# mother_card_17.net
KiCad netlist of a schematic drawn in EAGLE
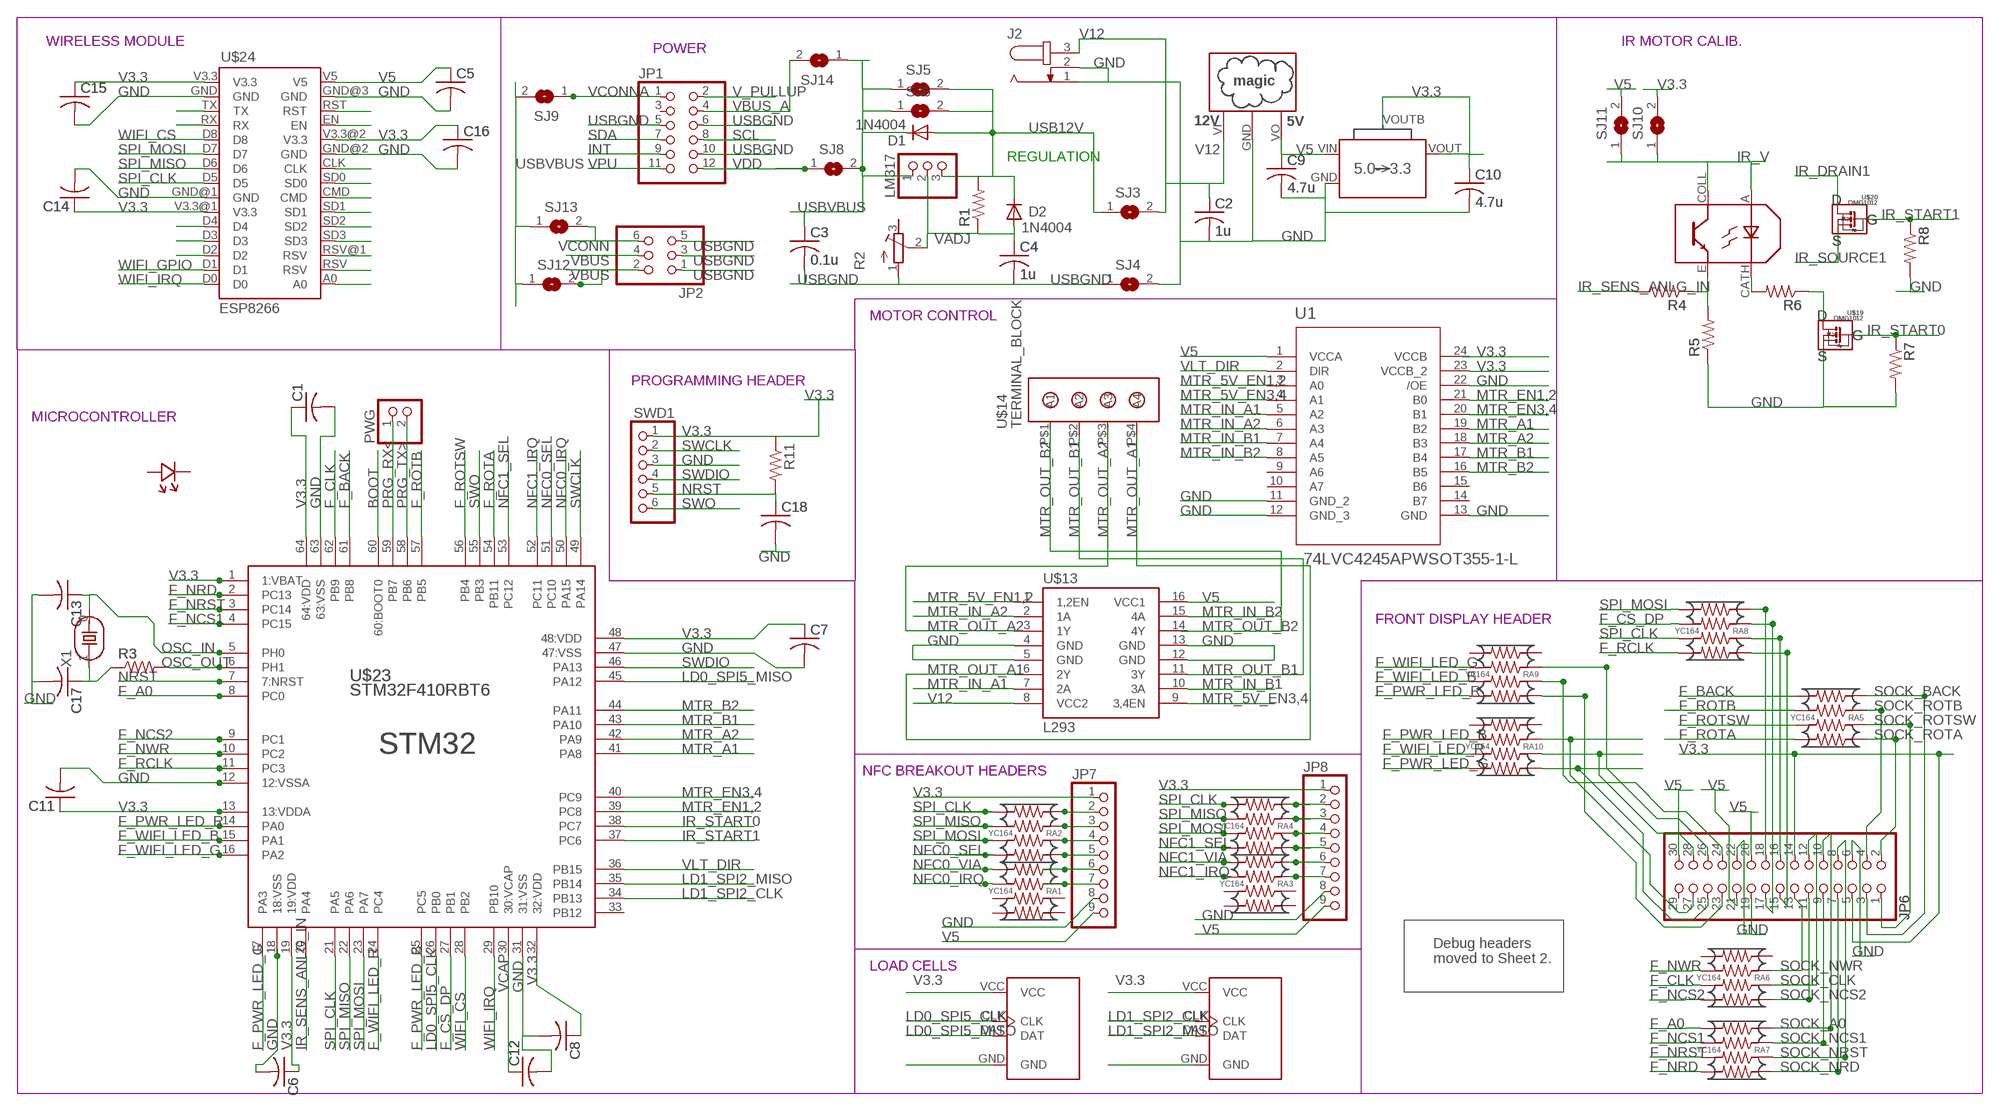
[diagram p0: schematic, sheet 1]
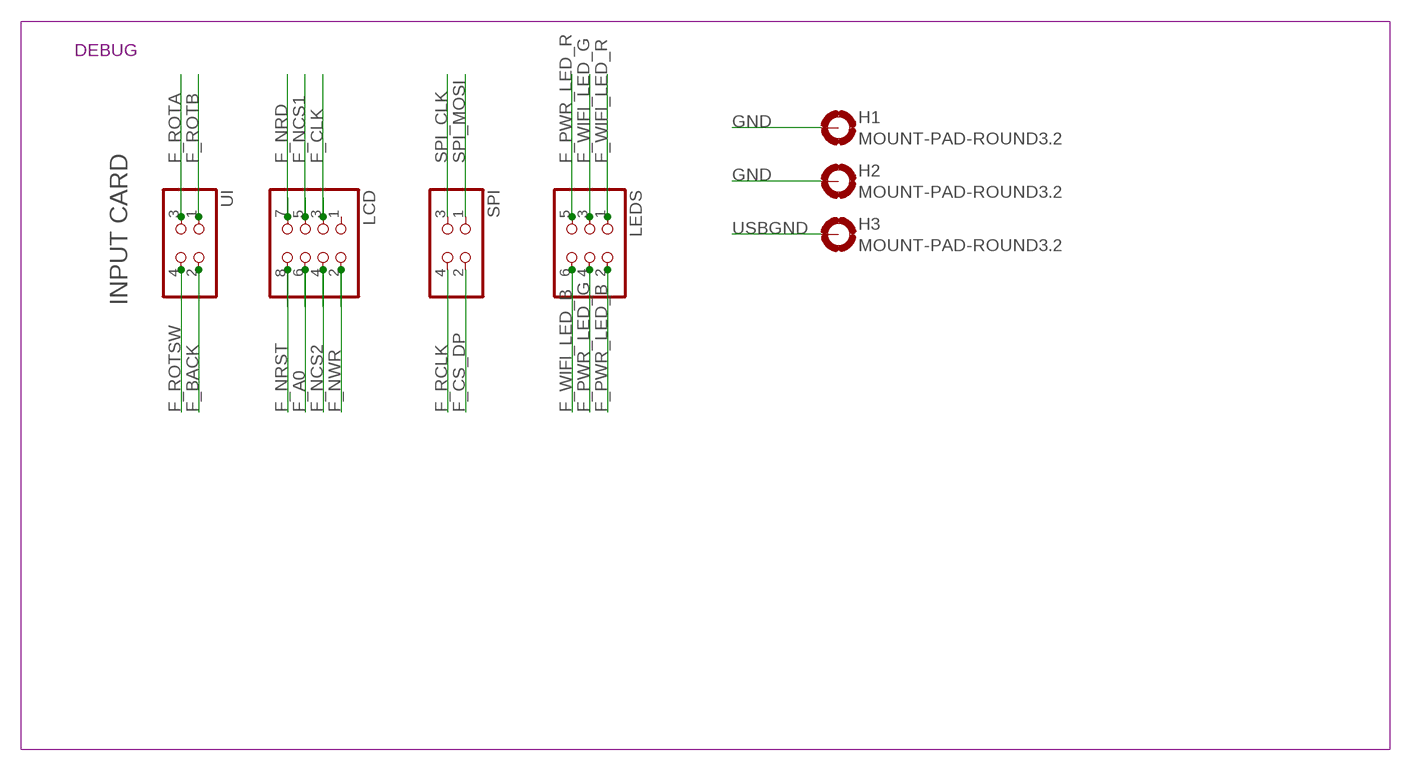
[diagram p1: schematic, sheet 2]

(export (version "E")
  (design (tool "Eeschema 10.0.6"))
  (components
    (comp (ref "H1")
      (value "MOUNT-PAD-ROUND3.2")
      (footprint "eagle-import:3,2-PAD")
      (libsource (lib "eagle-import") (part "MOUNT-PAD-ROUND3.2"))
    )
    (comp (ref "H2")
      (value "MOUNT-PAD-ROUND3.2")
      (footprint "eagle-import:3,2-PAD")
      (libsource (lib "eagle-import") (part "MOUNT-PAD-ROUND3.2"))
    )
    (comp (ref "H3")
      (value "MOUNT-PAD-ROUND3.2")
      (footprint "eagle-import:3,2-PAD")
      (libsource (lib "eagle-import") (part "MOUNT-PAD-ROUND3.2"))
    )
    (comp (ref "LCD")
      (value "PINHD-2X4")
      (footprint "eagle-import:2X04")
      (libsource (lib "eagle-import") (part "PINHD-2X4"))
    )
    (comp (ref "LEDS")
      (value "PINHD-2X3")
      (footprint "eagle-import:2X03")
      (libsource (lib "eagle-import") (part "PINHD-2X3"))
    )
    (comp (ref "SPI")
      (value "PINHD-2X2")
      (footprint "eagle-import:2X02")
      (libsource (lib "eagle-import") (part "PINHD-2X2"))
    )
    (comp (ref "UI")
      (value "PINHD-2X2")
      (footprint "eagle-import:2X02")
      (libsource (lib "eagle-import") (part "PINHD-2X2"))
    )
    (comp (ref "C1")
      (value "C-USC0805")
      (footprint "eagle-import:C0805")
      (libsource (lib "eagle-import") (part "C-USC0805"))
    )
    (comp (ref "C2")
      (value "1u")
      (footprint "eagle-import:C0805")
      (libsource (lib "eagle-import") (part "C-USC0805"))
    )
    (comp (ref "C3")
      (value "0.1u")
      (footprint "eagle-import:C0805")
      (libsource (lib "eagle-import") (part "C-USC0805"))
    )
    (comp (ref "C4")
      (value "1u")
      (footprint "eagle-import:C0805")
      (libsource (lib "eagle-import") (part "C-USC0805"))
    )
    (comp (ref "C5")
      (value "C-USC0805")
      (footprint "eagle-import:C0805")
      (libsource (lib "eagle-import") (part "C-USC0805"))
    )
    (comp (ref "C6")
      (value "C-USC0805")
      (footprint "eagle-import:C0805")
      (libsource (lib "eagle-import") (part "C-USC0805"))
    )
    (comp (ref "C7")
      (value "C-USC0805")
      (footprint "eagle-import:C0805")
      (libsource (lib "eagle-import") (part "C-USC0805"))
    )
    (comp (ref "C8")
      (value "C-USC0805")
      (footprint "eagle-import:C0805")
      (libsource (lib "eagle-import") (part "C-USC0805"))
    )
    (comp (ref "C9")
      (value "4.7u")
      (footprint "eagle-import:C0805")
      (libsource (lib "eagle-import") (part "C-USC0805"))
    )
    (comp (ref "C10")
      (value "4.7u")
      (footprint "eagle-import:C0805")
      (libsource (lib "eagle-import") (part "C-USC0805"))
    )
    (comp (ref "C11")
      (value "C-USC0805")
      (footprint "eagle-import:C0805")
      (libsource (lib "eagle-import") (part "C-USC0805"))
    )
    (comp (ref "C12")
      (value "C-USC0805")
      (footprint "eagle-import:C0805")
      (libsource (lib "eagle-import") (part "C-USC0805"))
    )
    (comp (ref "C13")
      (value "C-USC0603")
      (footprint "eagle-import:C0603")
      (libsource (lib "eagle-import") (part "C-USC0603"))
    )
    (comp (ref "C14")
      (value "C-USC0805")
      (footprint "eagle-import:C0805")
      (libsource (lib "eagle-import") (part "C-USC0805"))
    )
    (comp (ref "C15")
      (value "C-USC0805")
      (footprint "eagle-import:C0805")
      (libsource (lib "eagle-import") (part "C-USC0805"))
    )
    (comp (ref "C16")
      (value "C-USC0805")
      (footprint "eagle-import:C0805")
      (libsource (lib "eagle-import") (part "C-USC0805"))
    )
    (comp (ref "C17")
      (value "C-USC0603")
      (footprint "eagle-import:C0603")
      (libsource (lib "eagle-import") (part "C-USC0603"))
    )
    (comp (ref "C18")
      (value "C-USC0805")
      (footprint "eagle-import:C0805")
      (libsource (lib "eagle-import") (part "C-USC0805"))
    )
    (comp (ref "D1")
      (value "1N4004")
      (footprint "eagle-import:DO41-10")
      (libsource (lib "eagle-import") (part "1N4004"))
    )
    (comp (ref "D2")
      (value "1N4004")
      (footprint "eagle-import:DO41-10")
      (libsource (lib "eagle-import") (part "1N4004"))
    )
    (comp (ref "J2")
      (value "JACK-PLUG0")
      (footprint "eagle-import:SPC4077")
      (libsource (lib "eagle-import") (part "JACK-PLUG0"))
    )
    (comp (ref "JP1")
      (value "PINHD-2X6")
      (footprint "eagle-import:2X06")
      (libsource (lib "eagle-import") (part "PINHD-2X6"))
    )
    (comp (ref "JP2")
      (value "PINHD-2X3")
      (footprint "eagle-import:2X03")
      (libsource (lib "eagle-import") (part "PINHD-2X3"))
    )
    (comp (ref "JP6")
      (value "PINHD-2X15/SOCK")
      (footprint "eagle-import:2X15_SOCK")
      (libsource (lib "eagle-import") (part "PINHD-2X15/SOCK"))
    )
    (comp (ref "JP7")
      (value "PINHD-1X9/90")
      (footprint "eagle-import:1X09_90")
      (libsource (lib "eagle-import") (part "PINHD-1X9/90"))
    )
    (comp (ref "JP8")
      (value "PINHD-1X9/90")
      (footprint "eagle-import:1X09_90")
      (libsource (lib "eagle-import") (part "PINHD-1X9/90"))
    )
    (comp (ref "LM317")
      (value "PINHD-1X3")
      (footprint "eagle-import:1X03")
      (libsource (lib "eagle-import") (part "PINHD-1X3"))
    )
    (comp (ref "PWG")
      (value "PINHD-1X2")
      (footprint "eagle-import:1X02")
      (libsource (lib "eagle-import") (part "PINHD-1X2"))
    )
    (comp (ref "R1")
      (value "R-US_R0805")
      (footprint "eagle-import:R0805")
      (libsource (lib "eagle-import") (part "seniorDesign_R-US_R0805"))
    )
    (comp (ref "R2")
      (value "R-TRIMM64W")
      (footprint "eagle-import:RTRIM64W")
      (libsource (lib "eagle-import") (part "R-TRIMM64W"))
    )
    (comp (ref "R3")
      (value "R-US_R0805")
      (footprint "eagle-import:R0805")
      (libsource (lib "eagle-import") (part "seniorDesign_R-US_R0805"))
    )
    (comp (ref "R4")
      (value "R-US_R0805")
      (footprint "eagle-import:R0805")
      (libsource (lib "eagle-import") (part "seniorDesign_R-US_R0805"))
    )
    (comp (ref "R5")
      (value "R-US_R0805")
      (footprint "eagle-import:R0805")
      (libsource (lib "eagle-import") (part "seniorDesign_R-US_R0805"))
    )
    (comp (ref "R6")
      (value "R-US_R0805")
      (footprint "eagle-import:R0805")
      (libsource (lib "eagle-import") (part "seniorDesign_R-US_R0805"))
    )
    (comp (ref "R7")
      (value "R-US_R0805")
      (footprint "eagle-import:R0805")
      (libsource (lib "eagle-import") (part "seniorDesign_R-US_R0805"))
    )
    (comp (ref "R8")
      (value "R-US_R0805")
      (footprint "eagle-import:R0805")
      (libsource (lib "eagle-import") (part "seniorDesign_R-US_R0805"))
    )
    (comp (ref "R11")
      (value "R-US_R0805")
      (footprint "eagle-import:R0805")
      (libsource (lib "eagle-import") (part "R-US_R0805"))
    )
    (comp (ref "RA1")
      (value "YC164")
      (footprint "eagle-import:YC164")
      (libsource (lib "eagle-import") (part "YC164"))
    )
    (comp (ref "RA2")
      (value "YC164")
      (footprint "eagle-import:YC164")
      (libsource (lib "eagle-import") (part "YC164"))
    )
    (comp (ref "RA3")
      (value "YC164")
      (footprint "eagle-import:YC164")
      (libsource (lib "eagle-import") (part "YC164"))
    )
    (comp (ref "RA4")
      (value "YC164")
      (footprint "eagle-import:YC164")
      (libsource (lib "eagle-import") (part "YC164"))
    )
    (comp (ref "RA5")
      (value "YC164")
      (footprint "eagle-import:YC164")
      (libsource (lib "eagle-import") (part "YC164"))
    )
    (comp (ref "RA6")
      (value "YC164")
      (footprint "eagle-import:YC164")
      (libsource (lib "eagle-import") (part "YC164"))
    )
    (comp (ref "RA7")
      (value "YC164")
      (footprint "eagle-import:YC164")
      (libsource (lib "eagle-import") (part "YC164"))
    )
    (comp (ref "RA8")
      (value "YC164")
      (footprint "eagle-import:YC164")
      (libsource (lib "eagle-import") (part "YC164"))
    )
    (comp (ref "RA9")
      (value "YC164")
      (footprint "eagle-import:YC164")
      (libsource (lib "eagle-import") (part "YC164"))
    )
    (comp (ref "RA10")
      (value "YC164")
      (footprint "eagle-import:YC164")
      (libsource (lib "eagle-import") (part "YC164"))
    )
    (comp (ref "SJ3") (value "SJ") (footprint "eagle-import:SJ") (libsource (lib "eagle-import") (part "SJ")))
    (comp (ref "SJ4") (value "SJ") (footprint "eagle-import:SJ") (libsource (lib "eagle-import") (part "SJ")))
    (comp (ref "SJ5") (value "SJ") (footprint "eagle-import:SJ") (libsource (lib "eagle-import") (part "SJ")))
    (comp (ref "SJ6") (value "SJ") (footprint "eagle-import:SJ") (libsource (lib "eagle-import") (part "SJ")))
    (comp (ref "SJ8") (value "SJ") (footprint "eagle-import:SJ") (libsource (lib "eagle-import") (part "SJ")))
    (comp (ref "SJ9") (value "SJ") (footprint "eagle-import:SJ") (libsource (lib "eagle-import") (part "SJ")))
    (comp (ref "SJ10")
      (value "SJ")
      (footprint "eagle-import:SJ")
      (libsource (lib "eagle-import") (part "SJ"))
    )
    (comp (ref "SJ11")
      (value "SJ")
      (footprint "eagle-import:SJ")
      (libsource (lib "eagle-import") (part "SJ"))
    )
    (comp (ref "SJ12")
      (value "SJ")
      (footprint "eagle-import:SJ")
      (libsource (lib "eagle-import") (part "SJ"))
    )
    (comp (ref "SJ13")
      (value "SJ")
      (footprint "eagle-import:SJ")
      (libsource (lib "eagle-import") (part "SJ"))
    )
    (comp (ref "SJ14")
      (value "SJ")
      (footprint "eagle-import:SJ")
      (libsource (lib "eagle-import") (part "SJ"))
    )
    (comp (ref "SWD1")
      (value "PINHD-1X6")
      (footprint "eagle-import:1X06")
      (libsource (lib "eagle-import") (part "PINHD-1X6"))
    )
    (comp (ref "U$12")
      (value "LED0603")
      (footprint "eagle-import:LED")
      (libsource (lib "eagle-import") (part "LED0603"))
    )
    (comp (ref "U$13")
      (value "L293")
      (footprint "eagle-import:DIL16")
      (libsource (lib "eagle-import") (part "L293"))
    )
    (comp (ref "U$14")
      (value "TERMINAL_BLOCK")
      (footprint "eagle-import:1X4_BLOCK")
      (libsource (lib "eagle-import") (part "TERMINAL_BLOCK"))
    )
    (comp (ref "U$15")
      (value "AP2114H")
      (footprint "eagle-import:AP2114H")
      (libsource (lib "eagle-import") (part "AP2114H"))
    )
    (comp (ref "U$16")
      (value "OKI-78SR-W36")
      (footprint "eagle-import:SIP3")
      (libsource (lib "eagle-import") (part "OKI-78SR-W36"))
    )
    (comp (ref "U$18")
      (value "TCRT5000")
      (footprint "eagle-import:TCRT5000")
      (libsource (lib "eagle-import") (part "TCRT5000"))
    )
    (comp (ref "U$19")
      (value "DMG1012")
      (footprint "eagle-import:SOT323")
      (libsource (lib "eagle-import") (part "DMG1012"))
    )
    (comp (ref "U$20")
      (value "DMG1012")
      (footprint "eagle-import:SOT323")
      (libsource (lib "eagle-import") (part "DMG1012"))
    )
    (comp (ref "U$21")
      (value "HX711")
      (footprint "eagle-import:HX711")
      (libsource (lib "eagle-import") (part "HX711"))
    )
    (comp (ref "U$22")
      (value "HX711")
      (footprint "eagle-import:HX711")
      (libsource (lib "eagle-import") (part "HX711"))
    )
    (comp (ref "U$23")
      (value "STM32F410RBT6")
      (footprint "eagle-import:QFP50P1200X1200X160-64N")
      (libsource (lib "eagle-import") (part "STM32F410RBT6"))
    )
    (comp (ref "U$24")
      (value "ESP8266")
      (footprint "eagle-import:ESP8266")
      (libsource (lib "eagle-import") (part "ESP8266"))
    )
    (comp (ref "U1")
      (value "74LVC4245APWSOT355-1-L")
      (footprint "eagle-import:SOT355-1-L")
      (fields (field (name "MANUFACTURER_PART_NUMBER") "74LVC4245APW"))
      (libsource (lib "eagle-import") (part "74LVC4245APWSOT355-1-L"))
    )
    (comp (ref "X1")
      (value "HC-49S_9B")
      (footprint "eagle-import:HC-49S_9B")
      (libsource (lib "eagle-import") (part "HC-49S_9B"))
    )
  )
  (nets
    (net (code "1") (name "BOOT") (class "Default")
      (node (ref "U$23") (pin "60") (pinfunction "60:BOOT0_60") (pintype "bidirectional"))
    )
    (net (code "2") (name "F_A0") (class "Default")
      (node (ref "LCD") (pin "6") (pinfunction "6_6") (pintype "passive"))
      (node (ref "RA7") (pin "P$4") (pinfunction "4_P$4") (pintype "passive"))
      (node (ref "U$23") (pin "8") (pinfunction "PC0_8") (pintype "bidirectional"))
    )
    (net (code "3") (name "F_BACK") (class "Default")
      (node (ref "RA5") (pin "P$4") (pinfunction "4_P$4") (pintype "passive"))
      (node (ref "U$23") (pin "61") (pinfunction "PB8_61") (pintype "bidirectional"))
      (node (ref "UI") (pin "2") (pinfunction "2_2") (pintype "passive"))
    )
    (net (code "4") (name "F_CLK") (class "Default")
      (node (ref "LCD") (pin "3") (pinfunction "3_3") (pintype "passive"))
      (node (ref "RA6") (pin "P$2") (pinfunction "2_P$2") (pintype "passive"))
      (node (ref "U$23") (pin "62") (pinfunction "PB9_62") (pintype "bidirectional"))
    )
    (net (code "5") (name "F_CS_DP") (class "Default")
      (node (ref "RA8") (pin "P$3") (pinfunction "3_P$3") (pintype "passive"))
      (node (ref "SPI") (pin "2") (pinfunction "2_2") (pintype "passive"))
      (node (ref "U$23") (pin "27") (pinfunction "PB1_27") (pintype "bidirectional"))
    )
    (net (code "6") (name "F_NCS1") (class "Default")
      (node (ref "LCD") (pin "5") (pinfunction "5_5") (pintype "passive"))
      (node (ref "RA7") (pin "P$3") (pinfunction "3_P$3") (pintype "passive"))
      (node (ref "U$23") (pin "4") (pinfunction "PC15_4") (pintype "bidirectional"))
    )
    (net (code "7") (name "F_NCS2") (class "Default")
      (node (ref "LCD") (pin "4") (pinfunction "4_4") (pintype "passive"))
      (node (ref "RA6") (pin "P$1") (pinfunction "1_P$1") (pintype "passive"))
      (node (ref "U$23") (pin "9") (pinfunction "PC1_9") (pintype "bidirectional"))
    )
    (net (code "8") (name "F_NRD") (class "Default")
      (node (ref "LCD") (pin "7") (pinfunction "7_7") (pintype "passive"))
      (node (ref "RA7") (pin "P$1") (pinfunction "1_P$1") (pintype "passive"))
      (node (ref "U$23") (pin "2") (pinfunction "PC13_2") (pintype "bidirectional"))
    )
    (net (code "9") (name "F_NRST") (class "Default")
      (node (ref "LCD") (pin "8") (pinfunction "8_8") (pintype "passive"))
      (node (ref "RA7") (pin "P$2") (pinfunction "2_P$2") (pintype "passive"))
      (node (ref "U$23") (pin "3") (pinfunction "PC14_3") (pintype "bidirectional"))
    )
    (net (code "10") (name "F_NWR") (class "Default")
      (node (ref "LCD") (pin "2") (pinfunction "2_2") (pintype "passive"))
      (node (ref "RA6") (pin "P$3") (pinfunction "3_P$3") (pintype "passive"))
      (node (ref "U$23") (pin "10") (pinfunction "PC2_10") (pintype "bidirectional"))
    )
    (net (code "11") (name "F_PWR_LED_B") (class "Default")
      (node (ref "LEDS") (pin "2") (pinfunction "2_2") (pintype "passive"))
      (node (ref "RA10") (pin "P$3") (pinfunction "3_P$3") (pintype "passive"))
      (node (ref "U$23") (pin "25") (pinfunction "PC5_25") (pintype "bidirectional"))
    )
    (net (code "12") (name "F_PWR_LED_G") (class "Default")
      (node (ref "LEDS") (pin "4") (pinfunction "4_4") (pintype "passive"))
      (node (ref "RA10") (pin "P$1") (pinfunction "1_P$1") (pintype "passive"))
      (node (ref "U$23") (pin "17") (pinfunction "PA3_17") (pintype "bidirectional"))
    )
    (net (code "13") (name "F_PWR_LED_R") (class "Default")
      (node (ref "LEDS") (pin "5") (pinfunction "5_5") (pintype "passive"))
      (node (ref "RA9") (pin "P$1") (pinfunction "1_P$1") (pintype "passive"))
      (node (ref "U$23") (pin "14") (pinfunction "PA0_14") (pintype "bidirectional"))
    )
    (net (code "14") (name "F_RCLK") (class "Default")
      (node (ref "RA8") (pin "P$1") (pinfunction "1_P$1") (pintype "passive"))
      (node (ref "SPI") (pin "4") (pinfunction "4_4") (pintype "passive"))
      (node (ref "U$23") (pin "11") (pinfunction "PC3_11") (pintype "bidirectional"))
    )
    (net (code "15") (name "F_ROTA") (class "Default")
      (node (ref "RA5") (pin "P$1") (pinfunction "1_P$1") (pintype "passive"))
      (node (ref "U$23") (pin "54") (pinfunction "PB11_54") (pintype "bidirectional"))
      (node (ref "UI") (pin "3") (pinfunction "3_3") (pintype "passive"))
    )
    (net (code "16") (name "F_ROTB") (class "Default")
      (node (ref "RA5") (pin "P$3") (pinfunction "3_P$3") (pintype "passive"))
      (node (ref "U$23") (pin "57") (pinfunction "PB5_57") (pintype "bidirectional"))
      (node (ref "UI") (pin "1") (pinfunction "1_1") (pintype "passive"))
    )
    (net (code "17") (name "F_ROTSW") (class "Default")
      (node (ref "RA5") (pin "P$2") (pinfunction "2_P$2") (pintype "passive"))
      (node (ref "U$23") (pin "56") (pinfunction "PB4_56") (pintype "bidirectional"))
      (node (ref "UI") (pin "4") (pinfunction "4_4") (pintype "passive"))
    )
    (net (code "18") (name "F_WIFI_LED_B") (class "Default")
      (node (ref "LEDS") (pin "6") (pinfunction "6_6") (pintype "passive"))
      (node (ref "RA9") (pin "P$2") (pinfunction "2_P$2") (pintype "passive"))
      (node (ref "U$23") (pin "15") (pinfunction "PA1_15") (pintype "bidirectional"))
    )
    (net (code "19") (name "F_WIFI_LED_G") (class "Default")
      (node (ref "LEDS") (pin "3") (pinfunction "3_3") (pintype "passive"))
      (node (ref "RA9") (pin "P$3") (pinfunction "3_P$3") (pintype "passive"))
      (node (ref "U$23") (pin "16") (pinfunction "PA2_16") (pintype "bidirectional"))
    )
    (net (code "20") (name "F_WIFI_LED_R") (class "Default")
      (node (ref "LEDS") (pin "1") (pinfunction "1_1") (pintype "passive"))
      (node (ref "RA10") (pin "P$2") (pinfunction "2_P$2") (pintype "passive"))
      (node (ref "U$23") (pin "24") (pinfunction "PC4_24") (pintype "bidirectional"))
    )
    (net (code "21") (name "GND") (class "Default")
      (node (ref "C1") (pin "2") (pinfunction "2_2") (pintype "passive"))
      (node (ref "C10") (pin "2") (pinfunction "2_2") (pintype "passive"))
      (node (ref "C11") (pin "2") (pinfunction "2_2") (pintype "passive"))
      (node (ref "C12") (pin "2") (pinfunction "2_2") (pintype "passive"))
      (node (ref "C13") (pin "2") (pinfunction "2_2") (pintype "passive"))
      (node (ref "C14") (pin "2") (pinfunction "2_2") (pintype "passive"))
      (node (ref "C15") (pin "2") (pinfunction "2_2") (pintype "passive"))
      (node (ref "C16") (pin "2") (pinfunction "2_2") (pintype "passive"))
      (node (ref "C17") (pin "2") (pinfunction "2_2") (pintype "passive"))
      (node (ref "C18") (pin "2") (pinfunction "2_2") (pintype "passive"))
      (node (ref "C2") (pin "2") (pinfunction "2_2") (pintype "passive"))
      (node (ref "C5") (pin "2") (pinfunction "2_2") (pintype "passive"))
      (node (ref "C6") (pin "2") (pinfunction "2_2") (pintype "passive"))
      (node (ref "C7") (pin "2") (pinfunction "2_2") (pintype "passive"))
      (node (ref "C8") (pin "2") (pinfunction "2_2") (pintype "passive"))
      (node (ref "C9") (pin "2") (pinfunction "2_2") (pintype "passive"))
      (node (ref "H1") (pin "B3,2") (pinfunction "MOUNT_B3,2") (pintype "passive"))
      (node (ref "H2") (pin "B3,2") (pinfunction "MOUNT_B3,2") (pintype "passive"))
      (node (ref "J2") (pin "1") (pinfunction "1_1") (pintype "passive"))
      (node (ref "J2") (pin "2") (pinfunction "2_2") (pintype "passive"))
      (node (ref "JP6") (pin "19") (pinfunction "19_19") (pintype "passive"))
      (node (ref "JP6") (pin "22") (pinfunction "22_22") (pintype "passive"))
      (node (ref "JP6") (pin "6") (pinfunction "6_6") (pintype "passive"))
      (node (ref "JP7") (pin "8") (pinfunction "8_8") (pintype "passive"))
      (node (ref "JP8") (pin "8") (pinfunction "8_8") (pintype "passive"))
      (node (ref "R5") (pin "1") (pinfunction "1_1") (pintype "passive"))
      (node (ref "R7") (pin "2") (pinfunction "2_2") (pintype "passive"))
      (node (ref "R8") (pin "2") (pinfunction "2_2") (pintype "passive"))
      (node (ref "SJ4") (pin "2") (pinfunction "2_2") (pintype "passive"))
      (node (ref "SWD1") (pin "3") (pinfunction "3_3") (pintype "passive"))
      (node (ref "U$13") (pin "12") (pinfunction "GND_12") (pintype "bidirectional"))
      (node (ref "U$13") (pin "13") (pinfunction "GND_13") (pintype "bidirectional"))
      (node (ref "U$13") (pin "4") (pinfunction "GND_4") (pintype "bidirectional"))
      (node (ref "U$13") (pin "5") (pinfunction "GND_5") (pintype "bidirectional"))
      (node (ref "U$15") (pin "GND") (pinfunction "GND_GND") (pintype "power_in"))
      (node (ref "U$16") (pin "GND") (pinfunction "P$2_GND") (pintype "power_in"))
      (node (ref "U$19") (pin "S") (pinfunction "S_S") (pintype "bidirectional"))
      (node (ref "U$21") (pin "GND") (pinfunction "GND_GND") (pintype "power_in"))
      (node (ref "U$22") (pin "GND") (pinfunction "GND_GND") (pintype "power_in"))
      (node (ref "U$23") (pin "12") (pinfunction "12:VSSA_12") (pintype "bidirectional"))
      (node (ref "U$23") (pin "18") (pinfunction "18:VSS_18") (pintype "bidirectional"))
      (node (ref "U$23") (pin "31") (pinfunction "31:VSS_31") (pintype "bidirectional"))
      (node (ref "U$23") (pin "47") (pinfunction "47:VSS_47") (pintype "bidirectional"))
      (node (ref "U$23") (pin "63") (pinfunction "63:VSS_63") (pintype "bidirectional"))
      (node (ref "U$24") (pin "GND") (pinfunction "GND_GND") (pintype "bidirectional"))
      (node (ref "U$24") (pin "GND@1") (pinfunction "GND_GND@1") (pintype "bidirectional"))
      (node (ref "U$24") (pin "GND@2") (pinfunction "GND_GND@2") (pintype "bidirectional"))
      (node (ref "U$24") (pin "GND@3") (pinfunction "GND_GND@3") (pintype "bidirectional"))
      (node (ref "U1") (pin "11") (pinfunction "GND_2_11") (pintype "power_in"))
      (node (ref "U1") (pin "12") (pinfunction "GND_3_12") (pintype "power_in"))
      (node (ref "U1") (pin "13") (pinfunction "GND_13") (pintype "power_in"))
      (node (ref "U1") (pin "22") (pinfunction "/OE_22") (pintype "input"))
    )
    (net (code "22") (name "INT") (class "Default")
      (node (ref "JP1") (pin "9") (pinfunction "9_9") (pintype "passive"))
    )
    (net (code "23") (name "IR_DRAIN1") (class "Default")
      (node (ref "U$20") (pin "D") (pinfunction "D_D") (pintype "bidirectional"))
    )
    (net (code "24") (name "IR_SENS_ANLG_IN") (class "Default")
      (node (ref "R4") (pin "2") (pinfunction "2_2") (pintype "passive"))
      (node (ref "U$23") (pin "20") (pinfunction "PA4_20") (pintype "bidirectional"))
    )
    (net (code "25") (name "IR_SOURCE1") (class "Default")
      (node (ref "U$20") (pin "S") (pinfunction "S_S") (pintype "bidirectional"))
    )
    (net (code "26") (name "IR_START0") (class "Default")
      (node (ref "R7") (pin "1") (pinfunction "1_1") (pintype "passive"))
      (node (ref "U$19") (pin "G") (pinfunction "G_G") (pintype "bidirectional"))
      (node (ref "U$23") (pin "38") (pinfunction "PC7_38") (pintype "bidirectional"))
    )
    (net (code "27") (name "IR_START1") (class "Default")
      (node (ref "R8") (pin "1") (pinfunction "1_1") (pintype "passive"))
      (node (ref "U$20") (pin "G") (pinfunction "G_G") (pintype "bidirectional"))
      (node (ref "U$23") (pin "37") (pinfunction "PC6_37") (pintype "bidirectional"))
    )
    (net (code "28") (name "IR_V") (class "Default")
      (node (ref "SJ10") (pin "1") (pinfunction "1_1") (pintype "passive"))
      (node (ref "SJ11") (pin "1") (pinfunction "1_1") (pintype "passive"))
      (node (ref "U$18") (pin "A") (pinfunction "A_A") (pintype "bidirectional"))
      (node (ref "U$18") (pin "COLL") (pinfunction "COLL_COLL") (pintype "bidirectional"))
    )
    (net (code "29") (name "LD0_SPI5_CLK") (class "Default")
      (node (ref "U$21") (pin "CLK") (pinfunction "CLK_CLK") (pintype "bidirectional"))
      (node (ref "U$23") (pin "26") (pinfunction "PB0_26") (pintype "bidirectional"))
    )
    (net (code "30") (name "LD0_SPI5_MISO") (class "Default")
      (node (ref "U$21") (pin "DAT") (pinfunction "DAT_DAT") (pintype "bidirectional"))
      (node (ref "U$23") (pin "45") (pinfunction "PA12_45") (pintype "bidirectional"))
    )
    (net (code "31") (name "LD1_SPI2_CLK") (class "Default")
      (node (ref "U$22") (pin "CLK") (pinfunction "CLK_CLK") (pintype "bidirectional"))
      (node (ref "U$23") (pin "34") (pinfunction "PB13_34") (pintype "bidirectional"))
    )
    (net (code "32") (name "LD1_SPI2_MISO") (class "Default")
      (node (ref "U$22") (pin "DAT") (pinfunction "DAT_DAT") (pintype "bidirectional"))
      (node (ref "U$23") (pin "35") (pinfunction "PB14_35") (pintype "bidirectional"))
    )
    (net (code "33") (name "MTR_5V_EN1,2") (class "Default")
      (node (ref "U$13") (pin "1") (pinfunction "1,2EN_1") (pintype "bidirectional"))
      (node (ref "U1") (pin "3") (pinfunction "A0_3") (pintype "bidirectional"))
    )
    (net (code "34") (name "MTR_5V_EN3,4") (class "Default")
      (node (ref "U$13") (pin "9") (pinfunction "3,4EN_9") (pintype "bidirectional"))
      (node (ref "U1") (pin "4") (pinfunction "A1_4") (pintype "bidirectional"))
    )
    (net (code "35") (name "MTR_A1") (class "Default")
      (node (ref "U$23") (pin "41") (pinfunction "PA8_41") (pintype "bidirectional"))
      (node (ref "U1") (pin "19") (pinfunction "B2_19") (pintype "bidirectional"))
    )
    (net (code "36") (name "MTR_A2") (class "Default")
      (node (ref "U$23") (pin "42") (pinfunction "PA9_42") (pintype "bidirectional"))
      (node (ref "U1") (pin "18") (pinfunction "B3_18") (pintype "bidirectional"))
    )
    (net (code "37") (name "MTR_B1") (class "Default")
      (node (ref "U$23") (pin "43") (pinfunction "PA10_43") (pintype "bidirectional"))
      (node (ref "U1") (pin "17") (pinfunction "B4_17") (pintype "bidirectional"))
    )
    (net (code "38") (name "MTR_B2") (class "Default")
      (node (ref "U$23") (pin "44") (pinfunction "PA11_44") (pintype "bidirectional"))
      (node (ref "U1") (pin "16") (pinfunction "B5_16") (pintype "bidirectional"))
    )
    (net (code "39") (name "MTR_EN1,2") (class "Default")
      (node (ref "U$23") (pin "39") (pinfunction "PC8_39") (pintype "bidirectional"))
      (node (ref "U1") (pin "21") (pinfunction "B0_21") (pintype "bidirectional"))
    )
    (net (code "40") (name "MTR_EN3,4") (class "Default")
      (node (ref "U$23") (pin "40") (pinfunction "PC9_40") (pintype "bidirectional"))
      (node (ref "U1") (pin "20") (pinfunction "B1_20") (pintype "bidirectional"))
    )
    (net (code "41") (name "MTR_IN_A1") (class "Default")
      (node (ref "U$13") (pin "7") (pinfunction "2A_7") (pintype "bidirectional"))
      (node (ref "U1") (pin "5") (pinfunction "A2_5") (pintype "bidirectional"))
    )
    (net (code "42") (name "MTR_IN_A2") (class "Default")
      (node (ref "U$13") (pin "2") (pinfunction "1A_2") (pintype "bidirectional"))
      (node (ref "U1") (pin "6") (pinfunction "A3_6") (pintype "bidirectional"))
    )
    (net (code "43") (name "MTR_IN_B1") (class "Default")
      (node (ref "U$13") (pin "10") (pinfunction "3A_10") (pintype "bidirectional"))
      (node (ref "U1") (pin "7") (pinfunction "A4_7") (pintype "bidirectional"))
    )
    (net (code "44") (name "MTR_IN_B2") (class "Default")
      (node (ref "U$13") (pin "15") (pinfunction "4A_15") (pintype "bidirectional"))
      (node (ref "U1") (pin "8") (pinfunction "A5_8") (pintype "bidirectional"))
    )
    (net (code "45") (name "MTR_OUT_A1") (class "Default")
      (node (ref "U$13") (pin "6") (pinfunction "2Y_6") (pintype "bidirectional"))
      (node (ref "U$14") (pin "P$4") (pinfunction "A4_P$4") (pintype "bidirectional"))
    )
    (net (code "46") (name "MTR_OUT_A2") (class "Default")
      (node (ref "U$13") (pin "3") (pinfunction "1Y_3") (pintype "bidirectional"))
      (node (ref "U$14") (pin "P$3") (pinfunction "A3_P$3") (pintype "bidirectional"))
    )
    (net (code "47") (name "MTR_OUT_B1") (class "Default")
      (node (ref "U$13") (pin "11") (pinfunction "3Y_11") (pintype "bidirectional"))
      (node (ref "U$14") (pin "P$2") (pinfunction "A2_P$2") (pintype "bidirectional"))
    )
    (net (code "48") (name "MTR_OUT_B2") (class "Default")
      (node (ref "U$13") (pin "14") (pinfunction "4Y_14") (pintype "bidirectional"))
      (node (ref "U$14") (pin "P$1") (pinfunction "A1_P$1") (pintype "bidirectional"))
    )
    (net (code "49") (name "NFC0_IRQ") (class "Default")
      (node (ref "RA1") (pin "P$3") (pinfunction "3_P$3") (pintype "passive"))
      (node (ref "U$23") (pin "50") (pinfunction "PA15_50") (pintype "bidirectional"))
    )
    (net (code "50") (name "NFC0_SEL") (class "Default")
      (node (ref "RA2") (pin "P$1") (pinfunction "1_P$1") (pintype "passive"))
      (node (ref "U$23") (pin "51") (pinfunction "PC10_51") (pintype "bidirectional"))
    )
    (net (code "51") (name "NFC0_VIA") (class "Default")
      (node (ref "RA1") (pin "P$4") (pinfunction "4_P$4") (pintype "passive"))
    )
    (net (code "52") (name "NFC1_IRQ") (class "Default")
      (node (ref "RA3") (pin "P$3") (pinfunction "3_P$3") (pintype "passive"))
      (node (ref "U$23") (pin "52") (pinfunction "PC11_52") (pintype "bidirectional"))
    )
    (net (code "53") (name "NFC1_SEL") (class "Default")
      (node (ref "RA4") (pin "P$1") (pinfunction "1_P$1") (pintype "passive"))
      (node (ref "U$23") (pin "53") (pinfunction "PC12_53") (pintype "bidirectional"))
    )
    (net (code "54") (name "NFC1_VIA") (class "Default")
      (node (ref "RA3") (pin "P$4") (pinfunction "4_P$4") (pintype "passive"))
    )
    (net (code "55") (name "NRST") (class "Default")
      (node (ref "C18") (pin "1") (pinfunction "1_1") (pintype "passive"))
      (node (ref "R11") (pin "2") (pinfunction "2_2") (pintype "passive"))
      (node (ref "SWD1") (pin "5") (pinfunction "5_5") (pintype "passive"))
      (node (ref "U$23") (pin "7") (pinfunction "7:NRST_7") (pintype "bidirectional"))
    )
    (net (code "56") (name "Net-(R4-Pad1)") (class "Default")
      (node (ref "R4") (pin "1") (pinfunction "1_1") (pintype "passive"))
      (node (ref "R5") (pin "2") (pinfunction "2_2") (pintype "passive"))
      (node (ref "U$18") (pin "E") (pinfunction "E_E") (pintype "bidirectional"))
    )
    (net (code "57") (name "Net-(R6-Pad1)") (class "Default")
      (node (ref "R6") (pin "1") (pinfunction "1_1") (pintype "passive"))
      (node (ref "U$19") (pin "D") (pinfunction "D_D") (pintype "bidirectional"))
    )
    (net (code "58") (name "Net-(R6-Pad2)") (class "Default")
      (node (ref "R6") (pin "2") (pinfunction "2_2") (pintype "passive"))
      (node (ref "U$18") (pin "CATH") (pinfunction "CATH_CATH") (pintype "bidirectional"))
    )
    (net (code "59") (name "Net-(RA1-33)") (class "Default")
      (node (ref "JP7") (pin "7") (pinfunction "7_7") (pintype "passive"))
      (node (ref "RA1") (pin "P$33") (pinfunction "33_P$33") (pintype "passive"))
    )
    (net (code "60") (name "Net-(RA1-44)") (class "Default")
      (node (ref "JP7") (pin "6") (pinfunction "6_6") (pintype "passive"))
      (node (ref "RA1") (pin "P$44") (pinfunction "44_P$44") (pintype "passive"))
    )
    (net (code "61") (name "Net-(RA2-11)") (class "Default")
      (node (ref "JP7") (pin "5") (pinfunction "5_5") (pintype "passive"))
      (node (ref "RA2") (pin "P$11") (pinfunction "11_P$11") (pintype "passive"))
    )
    (net (code "62") (name "Net-(RA2-22)") (class "Default")
      (node (ref "JP7") (pin "4") (pinfunction "4_4") (pintype "passive"))
      (node (ref "RA2") (pin "P$22") (pinfunction "22_P$22") (pintype "passive"))
    )
    (net (code "63") (name "Net-(RA2-33)") (class "Default")
      (node (ref "JP7") (pin "3") (pinfunction "3_3") (pintype "passive"))
      (node (ref "RA2") (pin "P$33") (pinfunction "33_P$33") (pintype "passive"))
    )
    (net (code "64") (name "Net-(RA2-44)") (class "Default")
      (node (ref "JP7") (pin "2") (pinfunction "2_2") (pintype "passive"))
      (node (ref "RA2") (pin "P$44") (pinfunction "44_P$44") (pintype "passive"))
    )
    (net (code "65") (name "Net-(RA3-33)") (class "Default")
      (node (ref "JP8") (pin "7") (pinfunction "7_7") (pintype "passive"))
      (node (ref "RA3") (pin "P$33") (pinfunction "33_P$33") (pintype "passive"))
    )
    (net (code "66") (name "Net-(RA3-44)") (class "Default")
      (node (ref "JP8") (pin "6") (pinfunction "6_6") (pintype "passive"))
      (node (ref "RA3") (pin "P$44") (pinfunction "44_P$44") (pintype "passive"))
    )
    (net (code "67") (name "Net-(RA4-11)") (class "Default")
      (node (ref "JP8") (pin "5") (pinfunction "5_5") (pintype "passive"))
      (node (ref "RA4") (pin "P$11") (pinfunction "11_P$11") (pintype "passive"))
    )
    (net (code "68") (name "Net-(RA4-22)") (class "Default")
      (node (ref "JP8") (pin "4") (pinfunction "4_4") (pintype "passive"))
      (node (ref "RA4") (pin "P$22") (pinfunction "22_P$22") (pintype "passive"))
    )
    (net (code "69") (name "Net-(RA4-33)") (class "Default")
      (node (ref "JP8") (pin "3") (pinfunction "3_3") (pintype "passive"))
      (node (ref "RA4") (pin "P$33") (pinfunction "33_P$33") (pintype "passive"))
    )
    (net (code "70") (name "Net-(RA4-44)") (class "Default")
      (node (ref "JP8") (pin "2") (pinfunction "2_2") (pintype "passive"))
      (node (ref "RA4") (pin "P$44") (pinfunction "44_P$44") (pintype "passive"))
    )
    (net (code "71") (name "Net-(RA8-11)") (class "Default")
      (node (ref "JP6") (pin "15") (pinfunction "15_15") (pintype "passive"))
      (node (ref "RA8") (pin "P$11") (pinfunction "11_P$11") (pintype "passive"))
    )
    (net (code "72") (name "Net-(RA8-22)") (class "Default")
      (node (ref "JP6") (pin "16") (pinfunction "16_16") (pintype "passive"))
      (node (ref "RA8") (pin "P$22") (pinfunction "22_P$22") (pintype "passive"))
    )
    (net (code "73") (name "Net-(RA8-33)") (class "Default")
      (node (ref "JP6") (pin "17") (pinfunction "17_17") (pintype "passive"))
      (node (ref "RA8") (pin "P$33") (pinfunction "33_P$33") (pintype "passive"))
    )
    (net (code "74") (name "Net-(RA8-44)") (class "Default")
      (node (ref "JP6") (pin "18") (pinfunction "18_18") (pintype "passive"))
      (node (ref "RA8") (pin "P$44") (pinfunction "44_P$44") (pintype "passive"))
    )
    (net (code "75") (name "Net-(RA9-11)") (class "Default")
      (node (ref "JP6") (pin "23") (pinfunction "23_23") (pintype "passive"))
      (node (ref "RA9") (pin "P$11") (pinfunction "11_P$11") (pintype "passive"))
    )
    (net (code "76") (name "Net-(RA9-22)") (class "Default")
      (node (ref "JP6") (pin "24") (pinfunction "24_24") (pintype "passive"))
      (node (ref "RA9") (pin "P$22") (pinfunction "22_P$22") (pintype "passive"))
    )
    (net (code "77") (name "Net-(RA9-33)") (class "Default")
      (node (ref "JP6") (pin "26") (pinfunction "26_26") (pintype "passive"))
      (node (ref "RA9") (pin "P$33") (pinfunction "33_P$33") (pintype "passive"))
    )
    (net (code "78") (name "Net-(RA10-11)") (class "Default")
      (node (ref "JP6") (pin "25") (pinfunction "25_25") (pintype "passive"))
      (node (ref "RA10") (pin "P$11") (pinfunction "11_P$11") (pintype "passive"))
    )
    (net (code "79") (name "Net-(RA10-22)") (class "Default")
      (node (ref "JP6") (pin "28") (pinfunction "28_28") (pintype "passive"))
      (node (ref "RA10") (pin "P$22") (pinfunction "22_P$22") (pintype "passive"))
    )
    (net (code "80") (name "Net-(RA10-33)") (class "Default")
      (node (ref "JP6") (pin "27") (pinfunction "27_27") (pintype "passive"))
      (node (ref "RA10") (pin "P$33") (pinfunction "33_P$33") (pintype "passive"))
    )
    (net (code "81") (name "Net-(U$23-PH1)") (class "Default")
      (node (ref "R3") (pin "2") (pinfunction "2_2") (pintype "passive"))
      (node (ref "U$23") (pin "6") (pinfunction "PH1_6") (pintype "bidirectional"))
    )
    (net (code "82") (name "OSC_IN") (class "Default")
      (node (ref "C13") (pin "1") (pinfunction "1_1") (pintype "passive"))
      (node (ref "U$23") (pin "5") (pinfunction "PH0_5") (pintype "bidirectional"))
      (node (ref "X1") (pin "0") (pinfunction "P$1_0") (pintype "bidirectional"))
    )
    (net (code "83") (name "OSC_OUT") (class "Default")
      (node (ref "C17") (pin "1") (pinfunction "1_1") (pintype "passive"))
      (node (ref "R3") (pin "1") (pinfunction "1_1") (pintype "passive"))
      (node (ref "X1") (pin "1") (pinfunction "P$2_1") (pintype "bidirectional"))
    )
    (net (code "84") (name "PRG_RX<") (class "Default")
      (node (ref "PWG") (pin "1") (pinfunction "1_1") (pintype "passive"))
      (node (ref "U$23") (pin "59") (pinfunction "PB7_59") (pintype "bidirectional"))
    )
    (net (code "85") (name "PRG_TX>") (class "Default")
      (node (ref "PWG") (pin "2") (pinfunction "2_2") (pintype "passive"))
      (node (ref "U$23") (pin "58") (pinfunction "PB6_58") (pintype "bidirectional"))
    )
    (net (code "86") (name "SCL") (class "Default")
      (node (ref "JP1") (pin "8") (pinfunction "8_8") (pintype "passive"))
    )
    (net (code "87") (name "SDA") (class "Default")
      (node (ref "JP1") (pin "7") (pinfunction "7_7") (pintype "passive"))
    )
    (net (code "88") (name "SOCK_A0") (class "Default")
      (node (ref "JP6") (pin "10") (pinfunction "10_10") (pintype "passive"))
      (node (ref "RA7") (pin "P$44") (pinfunction "44_P$44") (pintype "passive"))
    )
    (net (code "89") (name "SOCK_BACK") (class "Default")
      (node (ref "JP6") (pin "3") (pinfunction "3_3") (pintype "passive"))
      (node (ref "RA5") (pin "P$44") (pinfunction "44_P$44") (pintype "passive"))
    )
    (net (code "90") (name "SOCK_CLK") (class "Default")
      (node (ref "JP6") (pin "12") (pinfunction "12_12") (pintype "passive"))
      (node (ref "RA6") (pin "P$22") (pinfunction "22_P$22") (pintype "passive"))
    )
    (net (code "91") (name "SOCK_NCS1") (class "Default")
      (node (ref "JP6") (pin "9") (pinfunction "9_9") (pintype "passive"))
      (node (ref "RA7") (pin "P$33") (pinfunction "33_P$33") (pintype "passive"))
    )
    (net (code "92") (name "SOCK_NCS2") (class "Default")
      (node (ref "JP6") (pin "11") (pinfunction "11_11") (pintype "passive"))
      (node (ref "RA6") (pin "P$11") (pinfunction "11_P$11") (pintype "passive"))
    )
    (net (code "93") (name "SOCK_NRD") (class "Default")
      (node (ref "JP6") (pin "7") (pinfunction "7_7") (pintype "passive"))
      (node (ref "RA7") (pin "P$11") (pinfunction "11_P$11") (pintype "passive"))
    )
    (net (code "94") (name "SOCK_NRST") (class "Default")
      (node (ref "JP6") (pin "8") (pinfunction "8_8") (pintype "passive"))
      (node (ref "RA7") (pin "P$22") (pinfunction "22_P$22") (pintype "passive"))
    )
    (net (code "95") (name "SOCK_NWR") (class "Default")
      (node (ref "JP6") (pin "13") (pinfunction "13_13") (pintype "passive"))
      (node (ref "RA6") (pin "P$33") (pinfunction "33_P$33") (pintype "passive"))
    )
    (net (code "96") (name "SOCK_ROTA") (class "Default")
      (node (ref "JP6") (pin "2") (pinfunction "2_2") (pintype "passive"))
      (node (ref "RA5") (pin "P$11") (pinfunction "11_P$11") (pintype "passive"))
    )
    (net (code "97") (name "SOCK_ROTB") (class "Default")
      (node (ref "JP6") (pin "4") (pinfunction "4_4") (pintype "passive"))
      (node (ref "RA5") (pin "P$33") (pinfunction "33_P$33") (pintype "passive"))
    )
    (net (code "98") (name "SOCK_ROTSW") (class "Default")
      (node (ref "JP6") (pin "1") (pinfunction "1_1") (pintype "passive"))
      (node (ref "RA5") (pin "P$22") (pinfunction "22_P$22") (pintype "passive"))
    )
    (net (code "99") (name "SPI_CLK") (class "Default")
      (node (ref "RA2") (pin "P$4") (pinfunction "4_P$4") (pintype "passive"))
      (node (ref "RA4") (pin "P$4") (pinfunction "4_P$4") (pintype "passive"))
      (node (ref "RA8") (pin "P$2") (pinfunction "2_P$2") (pintype "passive"))
      (node (ref "SPI") (pin "3") (pinfunction "3_3") (pintype "passive"))
      (node (ref "U$23") (pin "21") (pinfunction "PA5_21") (pintype "bidirectional"))
      (node (ref "U$24") (pin "D5") (pinfunction "D5_D5") (pintype "bidirectional"))
    )
    (net (code "100") (name "SPI_MISO") (class "Default")
      (node (ref "RA2") (pin "P$3") (pinfunction "3_P$3") (pintype "passive"))
      (node (ref "RA4") (pin "P$3") (pinfunction "3_P$3") (pintype "passive"))
      (node (ref "U$23") (pin "22") (pinfunction "PA6_22") (pintype "bidirectional"))
      (node (ref "U$24") (pin "D6") (pinfunction "D6_D6") (pintype "bidirectional"))
    )
    (net (code "101") (name "SPI_MOSI") (class "Default")
      (node (ref "RA2") (pin "P$2") (pinfunction "2_P$2") (pintype "passive"))
      (node (ref "RA4") (pin "P$2") (pinfunction "2_P$2") (pintype "passive"))
      (node (ref "RA8") (pin "P$4") (pinfunction "4_P$4") (pintype "passive"))
      (node (ref "SPI") (pin "1") (pinfunction "1_1") (pintype "passive"))
      (node (ref "U$23") (pin "23") (pinfunction "PA7_23") (pintype "bidirectional"))
      (node (ref "U$24") (pin "D7") (pinfunction "D7_D7") (pintype "bidirectional"))
    )
    (net (code "102") (name "SWCLK") (class "Default")
      (node (ref "SWD1") (pin "2") (pinfunction "2_2") (pintype "passive"))
      (node (ref "U$23") (pin "49") (pinfunction "PA14_49") (pintype "bidirectional"))
    )
    (net (code "103") (name "SWDIO") (class "Default")
      (node (ref "SWD1") (pin "4") (pinfunction "4_4") (pintype "passive"))
      (node (ref "U$23") (pin "46") (pinfunction "PA13_46") (pintype "bidirectional"))
    )
    (net (code "104") (name "SWO") (class "Default")
      (node (ref "SWD1") (pin "6") (pinfunction "6_6") (pintype "passive"))
      (node (ref "U$23") (pin "55") (pinfunction "PB3_55") (pintype "bidirectional"))
    )
    (net (code "105") (name "USB12V") (class "Default")
      (node (ref "D1") (pin "A") (pinfunction "A_A") (pintype "passive"))
      (node (ref "D2") (pin "C") (pinfunction "C_C") (pintype "passive"))
      (node (ref "LM317") (pin "3") (pinfunction "3_3") (pintype "passive"))
      (node (ref "R1") (pin "2") (pinfunction "2_2") (pintype "passive"))
      (node (ref "SJ3") (pin "1") (pinfunction "1_1") (pintype "passive"))
      (node (ref "SJ5") (pin "2") (pinfunction "2_2") (pintype "passive"))
      (node (ref "SJ6") (pin "2") (pinfunction "2_2") (pintype "passive"))
    )
    (net (code "106") (name "USBGND") (class "Default")
      (node (ref "C3") (pin "2") (pinfunction "2_2") (pintype "passive"))
      (node (ref "C4") (pin "2") (pinfunction "2_2") (pintype "passive"))
      (node (ref "H3") (pin "B3,2") (pinfunction "MOUNT_B3,2") (pintype "passive"))
      (node (ref "JP1") (pin "10") (pinfunction "10_10") (pintype "passive"))
      (node (ref "JP1") (pin "5") (pinfunction "5_5") (pintype "passive"))
      (node (ref "JP1") (pin "6") (pinfunction "6_6") (pintype "passive"))
      (node (ref "JP2") (pin "1") (pinfunction "1_1") (pintype "passive"))
      (node (ref "JP2") (pin "3") (pinfunction "3_3") (pintype "passive"))
      (node (ref "JP2") (pin "5") (pinfunction "5_5") (pintype "passive"))
      (node (ref "R2") (pin "1") (pinfunction "A_1") (pintype "passive"))
      (node (ref "SJ4") (pin "1") (pinfunction "1_1") (pintype "passive"))
    )
    (net (code "107") (name "USBVBUS") (class "Default")
      (node (ref "C3") (pin "1") (pinfunction "1_1") (pintype "passive"))
      (node (ref "D1") (pin "C") (pinfunction "C_C") (pintype "passive"))
      (node (ref "LM317") (pin "1") (pinfunction "1_1") (pintype "passive"))
      (node (ref "SJ12") (pin "1") (pinfunction "1_1") (pintype "passive"))
      (node (ref "SJ13") (pin "1") (pinfunction "1_1") (pintype "passive"))
      (node (ref "SJ14") (pin "1") (pinfunction "1_1") (pintype "passive"))
      (node (ref "SJ5") (pin "1") (pinfunction "1_1") (pintype "passive"))
      (node (ref "SJ6") (pin "1") (pinfunction "1_1") (pintype "passive"))
      (node (ref "SJ8") (pin "2") (pinfunction "2_2") (pintype "passive"))
      (node (ref "SJ9") (pin "2") (pinfunction "2_2") (pintype "passive"))
    )
    (net (code "108") (name "V3.3") (class "Default")
      (node (ref "C1") (pin "1") (pinfunction "1_1") (pintype "passive"))
      (node (ref "C10") (pin "1") (pinfunction "1_1") (pintype "passive"))
      (node (ref "C11") (pin "1") (pinfunction "1_1") (pintype "passive"))
      (node (ref "C14") (pin "1") (pinfunction "1_1") (pintype "passive"))
      (node (ref "C15") (pin "1") (pinfunction "1_1") (pintype "passive"))
      (node (ref "C16") (pin "1") (pinfunction "1_1") (pintype "passive"))
      (node (ref "C6") (pin "1") (pinfunction "1_1") (pintype "passive"))
      (node (ref "C7") (pin "1") (pinfunction "1_1") (pintype "passive"))
      (node (ref "C8") (pin "1") (pinfunction "1_1") (pintype "passive"))
      (node (ref "JP6") (pin "14") (pinfunction "14_14") (pintype "passive"))
      (node (ref "JP6") (pin "5") (pinfunction "5_5") (pintype "passive"))
      (node (ref "JP7") (pin "1") (pinfunction "1_1") (pintype "passive"))
      (node (ref "JP8") (pin "1") (pinfunction "1_1") (pintype "passive"))
      (node (ref "R11") (pin "1") (pinfunction "1_1") (pintype "passive"))
      (node (ref "SJ10") (pin "2") (pinfunction "2_2") (pintype "passive"))
      (node (ref "SWD1") (pin "1") (pinfunction "1_1") (pintype "passive"))
      (node (ref "U$15") (pin "VOUT") (pinfunction "VO_VOUT") (pintype "output"))
      (node (ref "U$15") (pin "VOUTB") (pinfunction "BODY_VOUTB") (pintype "open_collector"))
      (node (ref "U$21") (pin "VCC") (pinfunction "VCC_VCC") (pintype "power_in"))
      (node (ref "U$22") (pin "VCC") (pinfunction "VCC_VCC") (pintype "power_in"))
      (node (ref "U$23") (pin "1") (pinfunction "1:VBAT_1") (pintype "bidirectional"))
      (node (ref "U$23") (pin "13") (pinfunction "13:VDDA_13") (pintype "bidirectional"))
      (node (ref "U$23") (pin "19") (pinfunction "19:VDD_19") (pintype "bidirectional"))
      (node (ref "U$23") (pin "32") (pinfunction "32:VDD_32") (pintype "bidirectional"))
      (node (ref "U$23") (pin "48") (pinfunction "48:VDD_48") (pintype "bidirectional"))
      (node (ref "U$23") (pin "64") (pinfunction "64:VDD_64") (pintype "bidirectional"))
      (node (ref "U$24") (pin "V3.3") (pinfunction "V3.3_V3.3") (pintype "bidirectional"))
      (node (ref "U$24") (pin "V3.3@1") (pinfunction "V3.3_V3.3@1") (pintype "bidirectional"))
      (node (ref "U$24") (pin "V3.3@2") (pinfunction "V3.3_V3.3@2") (pintype "bidirectional"))
      (node (ref "U1") (pin "23") (pinfunction "VCCB_2_23") (pintype "power_in"))
      (node (ref "U1") (pin "24") (pinfunction "VCCB_24") (pintype "power_in"))
    )
    (net (code "109") (name "V5") (class "Default")
      (node (ref "C5") (pin "1") (pinfunction "1_1") (pintype "passive"))
      (node (ref "C9") (pin "1") (pinfunction "1_1") (pintype "passive"))
      (node (ref "JP6") (pin "20") (pinfunction "20_20") (pintype "passive"))
      (node (ref "JP6") (pin "21") (pinfunction "21_21") (pintype "passive"))
      (node (ref "JP6") (pin "30") (pinfunction "30_30") (pintype "passive"))
      (node (ref "JP7") (pin "9") (pinfunction "9_9") (pintype "passive"))
      (node (ref "JP8") (pin "9") (pinfunction "9_9") (pintype "passive"))
      (node (ref "SJ11") (pin "2") (pinfunction "2_2") (pintype "passive"))
      (node (ref "U$13") (pin "16") (pinfunction "VCC1_16") (pintype "bidirectional"))
      (node (ref "U$15") (pin "VIN") (pinfunction "VI_VIN") (pintype "input"))
      (node (ref "U$16") (pin "VO") (pinfunction "P$3_VO") (pintype "output"))
      (node (ref "U$24") (pin "V5") (pinfunction "V5_V5") (pintype "bidirectional"))
      (node (ref "U1") (pin "1") (pinfunction "VCCA_1") (pintype "power_in"))
    )
    (net (code "110") (name "V12") (class "Default")
      (node (ref "C2") (pin "1") (pinfunction "1_1") (pintype "passive"))
      (node (ref "J2") (pin "3") (pinfunction "3_3") (pintype "passive"))
      (node (ref "SJ3") (pin "2") (pinfunction "2_2") (pintype "passive"))
      (node (ref "U$13") (pin "8") (pinfunction "VCC2_8") (pintype "bidirectional"))
      (node (ref "U$16") (pin "VI") (pinfunction "P$1_VI") (pintype "input"))
    )
    (net (code "111") (name "VADJ") (class "Default")
      (node (ref "C4") (pin "1") (pinfunction "1_1") (pintype "passive"))
      (node (ref "D2") (pin "A") (pinfunction "A_A") (pintype "passive"))
      (node (ref "LM317") (pin "2") (pinfunction "2_2") (pintype "passive"))
      (node (ref "R1") (pin "1") (pinfunction "1_1") (pintype "passive"))
      (node (ref "R2") (pin "2") (pinfunction "S_2") (pintype "passive"))
    )
    (net (code "112") (name "VBUS") (class "Default")
      (node (ref "JP2") (pin "2") (pinfunction "2_2") (pintype "passive"))
      (node (ref "JP2") (pin "4") (pinfunction "4_4") (pintype "passive"))
      (node (ref "SJ12") (pin "2") (pinfunction "2_2") (pintype "passive"))
    )
    (net (code "113") (name "VBUS_A") (class "Default")
      (node (ref "JP1") (pin "4") (pinfunction "4_4") (pintype "passive"))
      (node (ref "SJ14") (pin "2") (pinfunction "2_2") (pintype "passive"))
    )
    (net (code "114") (name "VCAP") (class "Default")
      (node (ref "C12") (pin "1") (pinfunction "1_1") (pintype "passive"))
      (node (ref "U$23") (pin "30") (pinfunction "30:VCAP_30") (pintype "bidirectional"))
    )
    (net (code "115") (name "VCONN") (class "Default")
      (node (ref "JP2") (pin "6") (pinfunction "6_6") (pintype "passive"))
      (node (ref "SJ13") (pin "2") (pinfunction "2_2") (pintype "passive"))
    )
    (net (code "116") (name "VCONNA") (class "Default")
      (node (ref "JP1") (pin "1") (pinfunction "1_1") (pintype "passive"))
      (node (ref "SJ9") (pin "1") (pinfunction "1_1") (pintype "passive"))
    )
    (net (code "117") (name "VDD") (class "Default")
      (node (ref "JP1") (pin "12") (pinfunction "12_12") (pintype "passive"))
      (node (ref "SJ8") (pin "1") (pinfunction "1_1") (pintype "passive"))
    )
    (net (code "118") (name "VLT_DIR") (class "Default")
      (node (ref "U$23") (pin "36") (pinfunction "PB15_36") (pintype "bidirectional"))
      (node (ref "U1") (pin "2") (pinfunction "DIR_2") (pintype "input"))
    )
    (net (code "119") (name "VPU") (class "Default")
      (node (ref "JP1") (pin "11") (pinfunction "11_11") (pintype "passive"))
    )
    (net (code "120") (name "V_PULLUP") (class "Default")
      (node (ref "JP1") (pin "2") (pinfunction "2_2") (pintype "passive"))
    )
    (net (code "121") (name "WIFI_CS") (class "Default")
      (node (ref "U$23") (pin "28") (pinfunction "PB2_28") (pintype "bidirectional"))
      (node (ref "U$24") (pin "D8") (pinfunction "D8_D8") (pintype "bidirectional"))
    )
    (net (code "122") (name "WIFI_GPIO") (class "Default")
      (node (ref "U$24") (pin "D1") (pinfunction "D1_D1") (pintype "bidirectional"))
    )
    (net (code "123") (name "WIFI_IRQ") (class "Default")
      (node (ref "U$23") (pin "29") (pinfunction "PB10_29") (pintype "bidirectional"))
      (node (ref "U$24") (pin "D0") (pinfunction "D0_D0") (pintype "bidirectional"))
    )
    (net (code "124") (name "unconnected-(JP1-Pad3)") (class "Default")
      (node (ref "JP1") (pin "3") (pinfunction "3_3") (pintype "passive"))
    )
    (net (code "125") (name "unconnected-(JP6-Pad29)") (class "Default")
      (node (ref "JP6") (pin "29") (pinfunction "29_29") (pintype "passive"))
    )
    (net (code "126") (name "unconnected-(LCD-Pad1)") (class "Default")
      (node (ref "LCD") (pin "1") (pinfunction "1_1") (pintype "passive"))
    )
    (net (code "127") (name "unconnected-(R2-E-Pad3)") (class "Default")
      (node (ref "R2") (pin "3") (pinfunction "E_3") (pintype "passive"))
    )
    (net (code "128") (name "unconnected-(RA1-1-PadP$1)") (class "Default")
      (node (ref "RA1") (pin "P$1") (pinfunction "1_P$1") (pintype "passive"))
    )
    (net (code "129") (name "unconnected-(RA1-2-PadP$2)") (class "Default")
      (node (ref "RA1") (pin "P$2") (pinfunction "2_P$2") (pintype "passive"))
    )
    (net (code "130") (name "unconnected-(RA1-11-PadP$11)") (class "Default")
      (node (ref "RA1") (pin "P$11") (pinfunction "11_P$11") (pintype "passive"))
    )
    (net (code "131") (name "unconnected-(RA1-22-PadP$22)") (class "Default")
      (node (ref "RA1") (pin "P$22") (pinfunction "22_P$22") (pintype "passive"))
    )
    (net (code "132") (name "unconnected-(RA3-1-PadP$1)") (class "Default")
      (node (ref "RA3") (pin "P$1") (pinfunction "1_P$1") (pintype "passive"))
    )
    (net (code "133") (name "unconnected-(RA3-2-PadP$2)") (class "Default")
      (node (ref "RA3") (pin "P$2") (pinfunction "2_P$2") (pintype "passive"))
    )
    (net (code "134") (name "unconnected-(RA3-11-PadP$11)") (class "Default")
      (node (ref "RA3") (pin "P$11") (pinfunction "11_P$11") (pintype "passive"))
    )
    (net (code "135") (name "unconnected-(RA3-22-PadP$22)") (class "Default")
      (node (ref "RA3") (pin "P$22") (pinfunction "22_P$22") (pintype "passive"))
    )
    (net (code "136") (name "unconnected-(RA6-4-PadP$4)") (class "Default")
      (node (ref "RA6") (pin "P$4") (pinfunction "4_P$4") (pintype "passive"))
    )
    (net (code "137") (name "unconnected-(RA6-44-PadP$44)") (class "Default")
      (node (ref "RA6") (pin "P$44") (pinfunction "44_P$44") (pintype "passive"))
    )
    (net (code "138") (name "unconnected-(RA9-4-PadP$4)") (class "Default")
      (node (ref "RA9") (pin "P$4") (pinfunction "4_P$4") (pintype "passive"))
    )
    (net (code "139") (name "unconnected-(RA9-44-PadP$44)") (class "Default")
      (node (ref "RA9") (pin "P$44") (pinfunction "44_P$44") (pintype "passive"))
    )
    (net (code "140") (name "unconnected-(RA10-4-PadP$4)") (class "Default")
      (node (ref "RA10") (pin "P$4") (pinfunction "4_P$4") (pintype "passive"))
    )
    (net (code "141") (name "unconnected-(RA10-44-PadP$44)") (class "Default")
      (node (ref "RA10") (pin "P$44") (pinfunction "44_P$44") (pintype "passive"))
    )
    (net (code "142") (name "unconnected-(U$12-AN-PadANODE)") (class "Default")
      (node (ref "U$12") (pin "ANODE") (pinfunction "AN_ANODE") (pintype "input"))
    )
    (net (code "143") (name "unconnected-(U$12-CA-PadCATHODE)") (class "Default")
      (node (ref "U$12") (pin "CATHODE") (pinfunction "CA_CATHODE") (pintype "output"))
    )
    (net (code "144") (name "unconnected-(U$23-PB12-Pad33)") (class "Default")
      (node (ref "U$23") (pin "33") (pinfunction "PB12_33") (pintype "bidirectional"))
    )
    (net (code "145") (name "unconnected-(U$24-PadA0)") (class "Default")
      (node (ref "U$24") (pin "A0") (pinfunction "A0_A0") (pintype "bidirectional"))
    )
    (net (code "146") (name "unconnected-(U$24-PadCLK)") (class "Default")
      (node (ref "U$24") (pin "CLK") (pinfunction "CLK_CLK") (pintype "bidirectional"))
    )
    (net (code "147") (name "unconnected-(U$24-PadCMD)") (class "Default")
      (node (ref "U$24") (pin "CMD") (pinfunction "CMD_CMD") (pintype "bidirectional"))
    )
    (net (code "148") (name "unconnected-(U$24-PadD2)") (class "Default")
      (node (ref "U$24") (pin "D2") (pinfunction "D2_D2") (pintype "bidirectional"))
    )
    (net (code "149") (name "unconnected-(U$24-PadD3)") (class "Default")
      (node (ref "U$24") (pin "D3") (pinfunction "D3_D3") (pintype "bidirectional"))
    )
    (net (code "150") (name "unconnected-(U$24-PadD4)") (class "Default")
      (node (ref "U$24") (pin "D4") (pinfunction "D4_D4") (pintype "bidirectional"))
    )
    (net (code "151") (name "unconnected-(U$24-PadEN)") (class "Default")
      (node (ref "U$24") (pin "EN") (pinfunction "EN_EN") (pintype "bidirectional"))
    )
    (net (code "152") (name "unconnected-(U$24-PadRST)") (class "Default")
      (node (ref "U$24") (pin "RST") (pinfunction "RST_RST") (pintype "bidirectional"))
    )
    (net (code "153") (name "unconnected-(U$24-PadRSV)") (class "Default")
      (node (ref "U$24") (pin "RSV") (pinfunction "RSV_RSV") (pintype "bidirectional"))
    )
    (net (code "154") (name "unconnected-(U$24-PadRX)") (class "Default")
      (node (ref "U$24") (pin "RX") (pinfunction "RX_RX") (pintype "bidirectional"))
    )
    (net (code "155") (name "unconnected-(U$24-PadSD0)") (class "Default")
      (node (ref "U$24") (pin "SD0") (pinfunction "SD0_SD0") (pintype "bidirectional"))
    )
    (net (code "156") (name "unconnected-(U$24-PadSD1)") (class "Default")
      (node (ref "U$24") (pin "SD1") (pinfunction "SD1_SD1") (pintype "bidirectional"))
    )
    (net (code "157") (name "unconnected-(U$24-PadSD2)") (class "Default")
      (node (ref "U$24") (pin "SD2") (pinfunction "SD2_SD2") (pintype "bidirectional"))
    )
    (net (code "158") (name "unconnected-(U$24-PadSD3)") (class "Default")
      (node (ref "U$24") (pin "SD3") (pinfunction "SD3_SD3") (pintype "bidirectional"))
    )
    (net (code "159") (name "unconnected-(U$24-PadTX)") (class "Default")
      (node (ref "U$24") (pin "TX") (pinfunction "TX_TX") (pintype "bidirectional"))
    )
    (net (code "160") (name "unconnected-(U$24-RSV-PadRSV@1)") (class "Default")
      (node (ref "U$24") (pin "RSV@1") (pinfunction "RSV_RSV@1") (pintype "bidirectional"))
    )
    (net (code "161") (name "unconnected-(U1-A6-Pad9)") (class "Default")
      (node (ref "U1") (pin "9") (pinfunction "A6_9") (pintype "bidirectional"))
    )
    (net (code "162") (name "unconnected-(U1-A7-Pad10)") (class "Default")
      (node (ref "U1") (pin "10") (pinfunction "A7_10") (pintype "bidirectional"))
    )
    (net (code "163") (name "unconnected-(U1-B6-Pad15)") (class "Default")
      (node (ref "U1") (pin "15") (pinfunction "B6_15") (pintype "bidirectional"))
    )
    (net (code "164") (name "unconnected-(U1-B7-Pad14)") (class "Default")
      (node (ref "U1") (pin "14") (pinfunction "B7_14") (pintype "bidirectional"))
    )
  )
)
